# DesignBlockTest.net
KiCad netlist of a schematic drawn in EAGLE
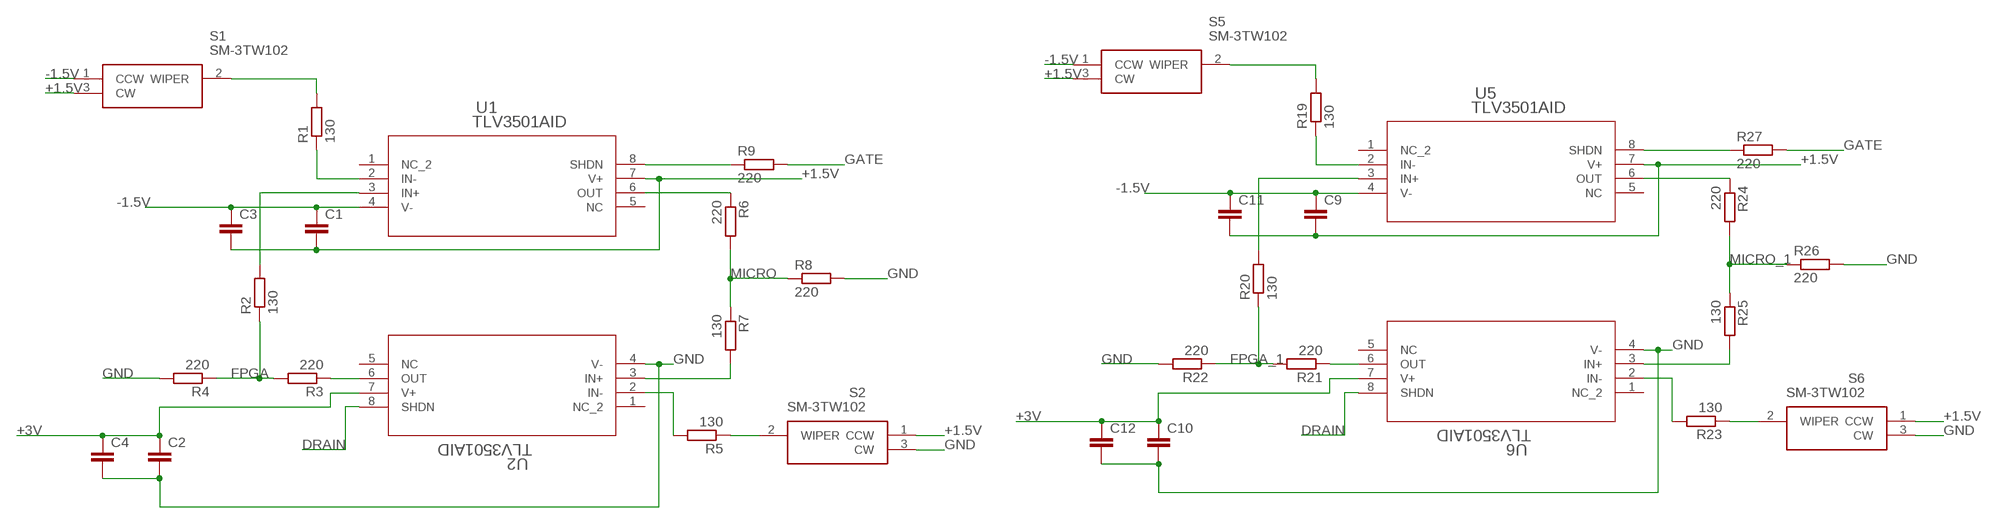
[diagram p0: schematic, sheet 1]

(export (version "E")
  (design (tool "Eeschema 10.0.6"))
  (components
    (comp (ref "C1")
      (value "C-EUC0805")
      (footprint "eagle-import:C0805")
      (libsource (lib "eagle-import") (part "C-EUC0805"))
    )
    (comp (ref "C2")
      (value "C-EUC0805")
      (footprint "eagle-import:C0805")
      (libsource (lib "eagle-import") (part "C-EUC0805"))
    )
    (comp (ref "C3")
      (value "C-EUC0805")
      (footprint "eagle-import:C0805")
      (libsource (lib "eagle-import") (part "C-EUC0805"))
    )
    (comp (ref "C4")
      (value "C-EUC0805")
      (footprint "eagle-import:C0805")
      (libsource (lib "eagle-import") (part "C-EUC0805"))
    )
    (comp (ref "C9")
      (value "C-EUC0805")
      (footprint "eagle-import:C0805")
      (libsource (lib "eagle-import") (part "C-EUC0805"))
    )
    (comp (ref "C10")
      (value "C-EUC0805")
      (footprint "eagle-import:C0805")
      (libsource (lib "eagle-import") (part "C-EUC0805"))
    )
    (comp (ref "C11")
      (value "C-EUC0805")
      (footprint "eagle-import:C0805")
      (libsource (lib "eagle-import") (part "C-EUC0805"))
    )
    (comp (ref "C12")
      (value "C-EUC0805")
      (footprint "eagle-import:C0805")
      (libsource (lib "eagle-import") (part "C-EUC0805"))
    )
    (comp (ref "R1")
      (value "130")
      (footprint "eagle-import:R0805")
      (libsource (lib "eagle-import") (part "R-EU_R0805"))
    )
    (comp (ref "R2")
      (value "130")
      (footprint "eagle-import:R0603")
      (libsource (lib "eagle-import") (part "R-EU_R0603"))
    )
    (comp (ref "R3")
      (value "220")
      (footprint "eagle-import:R0805")
      (libsource (lib "eagle-import") (part "R-EU_R0805"))
    )
    (comp (ref "R4")
      (value "220")
      (footprint "eagle-import:R0805")
      (libsource (lib "eagle-import") (part "R-EU_R0805"))
    )
    (comp (ref "R5")
      (value "130")
      (footprint "eagle-import:R0805")
      (libsource (lib "eagle-import") (part "R-EU_R0805"))
    )
    (comp (ref "R6")
      (value "220")
      (footprint "eagle-import:R0805")
      (libsource (lib "eagle-import") (part "R-EU_R0805"))
    )
    (comp (ref "R7")
      (value "130")
      (footprint "eagle-import:R0805")
      (libsource (lib "eagle-import") (part "R-EU_R0805"))
    )
    (comp (ref "R8")
      (value "220")
      (footprint "eagle-import:R0805")
      (libsource (lib "eagle-import") (part "R-EU_R0805"))
    )
    (comp (ref "R9")
      (value "220")
      (footprint "eagle-import:R0805")
      (libsource (lib "eagle-import") (part "R-EU_R0805"))
    )
    (comp (ref "R19")
      (value "130")
      (footprint "eagle-import:R0805")
      (libsource (lib "eagle-import") (part "R-EU_R0805"))
    )
    (comp (ref "R20")
      (value "130")
      (footprint "eagle-import:R0603")
      (libsource (lib "eagle-import") (part "R-EU_R0603"))
    )
    (comp (ref "R21")
      (value "220")
      (footprint "eagle-import:R0805")
      (libsource (lib "eagle-import") (part "R-EU_R0805"))
    )
    (comp (ref "R22")
      (value "220")
      (footprint "eagle-import:R0805")
      (libsource (lib "eagle-import") (part "R-EU_R0805"))
    )
    (comp (ref "R23")
      (value "130")
      (footprint "eagle-import:R0805")
      (libsource (lib "eagle-import") (part "R-EU_R0805"))
    )
    (comp (ref "R24")
      (value "220")
      (footprint "eagle-import:R0805")
      (libsource (lib "eagle-import") (part "R-EU_R0805"))
    )
    (comp (ref "R25")
      (value "130")
      (footprint "eagle-import:R0805")
      (libsource (lib "eagle-import") (part "R-EU_R0805"))
    )
    (comp (ref "R26")
      (value "220")
      (footprint "eagle-import:R0805")
      (libsource (lib "eagle-import") (part "R-EU_R0805"))
    )
    (comp (ref "R27")
      (value "220")
      (footprint "eagle-import:R0805")
      (libsource (lib "eagle-import") (part "R-EU_R0805"))
    )
    (comp (ref "S1")
      (value "SM-3TW102")
      (footprint "eagle-import:SM3TW102")
      (fields (field (name "MOUSER_PART_NUMBER") "229-SM-3TW102"))
      (libsource (lib "eagle-import") (part "SM-3TW102"))
    )
    (comp (ref "S2")
      (value "SM-3TW102")
      (footprint "eagle-import:SM3TW102")
      (fields (field (name "MOUSER_PART_NUMBER") "229-SM-3TW102"))
      (libsource (lib "eagle-import") (part "SM-3TW102"))
    )
    (comp (ref "S5")
      (value "SM-3TW102")
      (footprint "eagle-import:SM3TW102")
      (fields (field (name "MOUSER_PART_NUMBER") "229-SM-3TW102"))
      (libsource (lib "eagle-import") (part "SM-3TW102"))
    )
    (comp (ref "S6")
      (value "SM-3TW102")
      (footprint "eagle-import:SM3TW102")
      (fields (field (name "MOUSER_PART_NUMBER") "229-SM-3TW102"))
      (libsource (lib "eagle-import") (part "SM-3TW102"))
    )
    (comp (ref "U1")
      (value "TLV3501AID")
      (footprint "eagle-import:D8")
      (fields (field (name "COPYRIGHT") "Copyright (C) 2022 Ultra Librarian. All rights reserved."))
      (libsource (lib "eagle-import") (part "TLV3501AID"))
    )
    (comp (ref "U2")
      (value "TLV3501AID")
      (footprint "eagle-import:D8")
      (fields (field (name "COPYRIGHT") "Copyright (C) 2022 Ultra Librarian. All rights reserved."))
      (libsource (lib "eagle-import") (part "TLV3501AID"))
    )
    (comp (ref "U5")
      (value "TLV3501AID")
      (footprint "eagle-import:D8")
      (fields (field (name "COPYRIGHT") "Copyright (C) 2022 Ultra Librarian. All rights reserved."))
      (libsource (lib "eagle-import") (part "TLV3501AID"))
    )
    (comp (ref "U6")
      (value "TLV3501AID")
      (footprint "eagle-import:D8")
      (fields (field (name "COPYRIGHT") "Copyright (C) 2022 Ultra Librarian. All rights reserved."))
      (libsource (lib "eagle-import") (part "TLV3501AID"))
    )
  )
  (nets
    (net (code "1") (name "/+1.5V") (class "Default")
      (node (ref "C1") (pin "2") (pinfunction "2_2") (pintype "passive"))
      (node (ref "C11") (pin "2") (pinfunction "2_2") (pintype "passive"))
      (node (ref "C3") (pin "2") (pinfunction "2_2") (pintype "passive"))
      (node (ref "C9") (pin "2") (pinfunction "2_2") (pintype "passive"))
      (node (ref "S1") (pin "3") (pinfunction "CW_3") (pintype "bidirectional"))
      (node (ref "S2") (pin "1") (pinfunction "CCW_1") (pintype "bidirectional"))
      (node (ref "S5") (pin "3") (pinfunction "CW_3") (pintype "bidirectional"))
      (node (ref "S6") (pin "1") (pinfunction "CCW_1") (pintype "bidirectional"))
      (node (ref "U1") (pin "7") (pinfunction "V+_7") (pintype "power_in"))
      (node (ref "U5") (pin "7") (pinfunction "V+_7") (pintype "power_in"))
    )
    (net (code "2") (name "/+3V") (class "Default")
      (node (ref "C10") (pin "1") (pinfunction "1_1") (pintype "passive"))
      (node (ref "C12") (pin "1") (pinfunction "1_1") (pintype "passive"))
      (node (ref "C2") (pin "1") (pinfunction "1_1") (pintype "passive"))
      (node (ref "C4") (pin "1") (pinfunction "1_1") (pintype "passive"))
      (node (ref "U2") (pin "7") (pinfunction "V+_7") (pintype "power_in"))
      (node (ref "U6") (pin "7") (pinfunction "V+_7") (pintype "power_in"))
    )
    (net (code "3") (name "/-1.5V") (class "Default")
      (node (ref "C1") (pin "1") (pinfunction "1_1") (pintype "passive"))
      (node (ref "C11") (pin "1") (pinfunction "1_1") (pintype "passive"))
      (node (ref "C3") (pin "1") (pinfunction "1_1") (pintype "passive"))
      (node (ref "C9") (pin "1") (pinfunction "1_1") (pintype "passive"))
      (node (ref "S1") (pin "1") (pinfunction "CCW_1") (pintype "bidirectional"))
      (node (ref "S5") (pin "1") (pinfunction "CCW_1") (pintype "bidirectional"))
      (node (ref "U1") (pin "4") (pinfunction "V-_4") (pintype "power_in"))
      (node (ref "U5") (pin "4") (pinfunction "V-_4") (pintype "power_in"))
    )
    (net (code "4") (name "/DRAIN") (class "Default")
      (node (ref "U2") (pin "8") (pinfunction "SHDN_8") (pintype "passive"))
      (node (ref "U6") (pin "8") (pinfunction "SHDN_8") (pintype "passive"))
    )
    (net (code "5") (name "/FPGA") (class "Default")
      (node (ref "R2") (pin "1") (pinfunction "1_1") (pintype "passive"))
      (node (ref "R3") (pin "2") (pinfunction "2_2") (pintype "passive"))
      (node (ref "R4") (pin "1") (pinfunction "1_1") (pintype "passive"))
    )
    (net (code "6") (name "/FPGA_1") (class "Default")
      (node (ref "R20") (pin "1") (pinfunction "1_1") (pintype "passive"))
      (node (ref "R21") (pin "2") (pinfunction "2_2") (pintype "passive"))
      (node (ref "R22") (pin "1") (pinfunction "1_1") (pintype "passive"))
    )
    (net (code "7") (name "/GATE") (class "Default")
      (node (ref "R27") (pin "2") (pinfunction "2_2") (pintype "passive"))
      (node (ref "R9") (pin "2") (pinfunction "2_2") (pintype "passive"))
    )
    (net (code "8") (name "/GND") (class "Default")
      (node (ref "C10") (pin "2") (pinfunction "2_2") (pintype "passive"))
      (node (ref "C12") (pin "2") (pinfunction "2_2") (pintype "passive"))
      (node (ref "C2") (pin "2") (pinfunction "2_2") (pintype "passive"))
      (node (ref "C4") (pin "2") (pinfunction "2_2") (pintype "passive"))
      (node (ref "R22") (pin "2") (pinfunction "2_2") (pintype "passive"))
      (node (ref "R26") (pin "2") (pinfunction "2_2") (pintype "passive"))
      (node (ref "R4") (pin "2") (pinfunction "2_2") (pintype "passive"))
      (node (ref "R8") (pin "2") (pinfunction "2_2") (pintype "passive"))
      (node (ref "S2") (pin "3") (pinfunction "CW_3") (pintype "bidirectional"))
      (node (ref "S6") (pin "3") (pinfunction "CW_3") (pintype "bidirectional"))
      (node (ref "U2") (pin "4") (pinfunction "V-_4") (pintype "power_in"))
      (node (ref "U6") (pin "4") (pinfunction "V-_4") (pintype "power_in"))
    )
    (net (code "9") (name "/MICRO") (class "Default")
      (node (ref "R6") (pin "2") (pinfunction "2_2") (pintype "passive"))
      (node (ref "R7") (pin "1") (pinfunction "1_1") (pintype "passive"))
      (node (ref "R8") (pin "1") (pinfunction "1_1") (pintype "passive"))
    )
    (net (code "10") (name "/MICRO_1") (class "Default")
      (node (ref "R24") (pin "2") (pinfunction "2_2") (pintype "passive"))
      (node (ref "R25") (pin "1") (pinfunction "1_1") (pintype "passive"))
      (node (ref "R26") (pin "1") (pinfunction "1_1") (pintype "passive"))
    )
    (net (code "11") (name "Net-(S1-WIPER)") (class "Default")
      (node (ref "R1") (pin "2") (pinfunction "2_2") (pintype "passive"))
      (node (ref "S1") (pin "2") (pinfunction "WIPER_2") (pintype "bidirectional"))
    )
    (net (code "12") (name "Net-(S2-WIPER)") (class "Default")
      (node (ref "R5") (pin "1") (pinfunction "1_1") (pintype "passive"))
      (node (ref "S2") (pin "2") (pinfunction "WIPER_2") (pintype "bidirectional"))
    )
    (net (code "13") (name "Net-(S5-WIPER)") (class "Default")
      (node (ref "R19") (pin "2") (pinfunction "2_2") (pintype "passive"))
      (node (ref "S5") (pin "2") (pinfunction "WIPER_2") (pintype "bidirectional"))
    )
    (net (code "14") (name "Net-(S6-WIPER)") (class "Default")
      (node (ref "R23") (pin "1") (pinfunction "1_1") (pintype "passive"))
      (node (ref "S6") (pin "2") (pinfunction "WIPER_2") (pintype "bidirectional"))
    )
    (net (code "15") (name "Net-(U1-IN+)") (class "Default")
      (node (ref "R2") (pin "2") (pinfunction "2_2") (pintype "passive"))
      (node (ref "U1") (pin "3") (pinfunction "IN+_3") (pintype "input"))
    )
    (net (code "16") (name "Net-(U1-IN-)") (class "Default")
      (node (ref "R1") (pin "1") (pinfunction "1_1") (pintype "passive"))
      (node (ref "U1") (pin "2") (pinfunction "IN-_2") (pintype "input"))
    )
    (net (code "17") (name "Net-(U1-OUT)") (class "Default")
      (node (ref "R6") (pin "1") (pinfunction "1_1") (pintype "passive"))
      (node (ref "U1") (pin "6") (pinfunction "OUT_6") (pintype "output"))
    )
    (net (code "18") (name "Net-(U1-SHDN)") (class "Default")
      (node (ref "R9") (pin "1") (pinfunction "1_1") (pintype "passive"))
      (node (ref "U1") (pin "8") (pinfunction "SHDN_8") (pintype "passive"))
    )
    (net (code "19") (name "Net-(U2-IN+)") (class "Default")
      (node (ref "R7") (pin "2") (pinfunction "2_2") (pintype "passive"))
      (node (ref "U2") (pin "3") (pinfunction "IN+_3") (pintype "input"))
    )
    (net (code "20") (name "Net-(U2-IN-)") (class "Default")
      (node (ref "R5") (pin "2") (pinfunction "2_2") (pintype "passive"))
      (node (ref "U2") (pin "2") (pinfunction "IN-_2") (pintype "input"))
    )
    (net (code "21") (name "Net-(U2-OUT)") (class "Default")
      (node (ref "R3") (pin "1") (pinfunction "1_1") (pintype "passive"))
      (node (ref "U2") (pin "6") (pinfunction "OUT_6") (pintype "output"))
    )
    (net (code "22") (name "Net-(U5-IN+)") (class "Default")
      (node (ref "R20") (pin "2") (pinfunction "2_2") (pintype "passive"))
      (node (ref "U5") (pin "3") (pinfunction "IN+_3") (pintype "input"))
    )
    (net (code "23") (name "Net-(U5-IN-)") (class "Default")
      (node (ref "R19") (pin "1") (pinfunction "1_1") (pintype "passive"))
      (node (ref "U5") (pin "2") (pinfunction "IN-_2") (pintype "input"))
    )
    (net (code "24") (name "Net-(U5-OUT)") (class "Default")
      (node (ref "R24") (pin "1") (pinfunction "1_1") (pintype "passive"))
      (node (ref "U5") (pin "6") (pinfunction "OUT_6") (pintype "output"))
    )
    (net (code "25") (name "Net-(U5-SHDN)") (class "Default")
      (node (ref "R27") (pin "1") (pinfunction "1_1") (pintype "passive"))
      (node (ref "U5") (pin "8") (pinfunction "SHDN_8") (pintype "passive"))
    )
    (net (code "26") (name "Net-(U6-IN+)") (class "Default")
      (node (ref "R25") (pin "2") (pinfunction "2_2") (pintype "passive"))
      (node (ref "U6") (pin "3") (pinfunction "IN+_3") (pintype "input"))
    )
    (net (code "27") (name "Net-(U6-IN-)") (class "Default")
      (node (ref "R23") (pin "2") (pinfunction "2_2") (pintype "passive"))
      (node (ref "U6") (pin "2") (pinfunction "IN-_2") (pintype "input"))
    )
    (net (code "28") (name "Net-(U6-OUT)") (class "Default")
      (node (ref "R21") (pin "1") (pinfunction "1_1") (pintype "passive"))
      (node (ref "U6") (pin "6") (pinfunction "OUT_6") (pintype "output"))
    )
    (net (code "29") (name "unconnected-(U1-NC-Pad5)") (class "Default")
      (node (ref "U1") (pin "5") (pinfunction "NC_5") (pintype "passive"))
    )
    (net (code "30") (name "unconnected-(U1-NC_2-Pad1)") (class "Default")
      (node (ref "U1") (pin "1") (pinfunction "NC_2_1") (pintype "passive"))
    )
    (net (code "31") (name "unconnected-(U2-NC-Pad5)") (class "Default")
      (node (ref "U2") (pin "5") (pinfunction "NC_5") (pintype "passive"))
    )
    (net (code "32") (name "unconnected-(U2-NC_2-Pad1)") (class "Default")
      (node (ref "U2") (pin "1") (pinfunction "NC_2_1") (pintype "passive"))
    )
    (net (code "33") (name "unconnected-(U5-NC-Pad5)") (class "Default")
      (node (ref "U5") (pin "5") (pinfunction "NC_5") (pintype "passive"))
    )
    (net (code "34") (name "unconnected-(U5-NC_2-Pad1)") (class "Default")
      (node (ref "U5") (pin "1") (pinfunction "NC_2_1") (pintype "passive"))
    )
    (net (code "35") (name "unconnected-(U6-NC-Pad5)") (class "Default")
      (node (ref "U6") (pin "5") (pinfunction "NC_5") (pintype "passive"))
    )
    (net (code "36") (name "unconnected-(U6-NC_2-Pad1)") (class "Default")
      (node (ref "U6") (pin "1") (pinfunction "NC_2_1") (pintype "passive"))
    )
  )
)
